# VCA822.net
KiCad netlist of a schematic drawn in Altium Designer
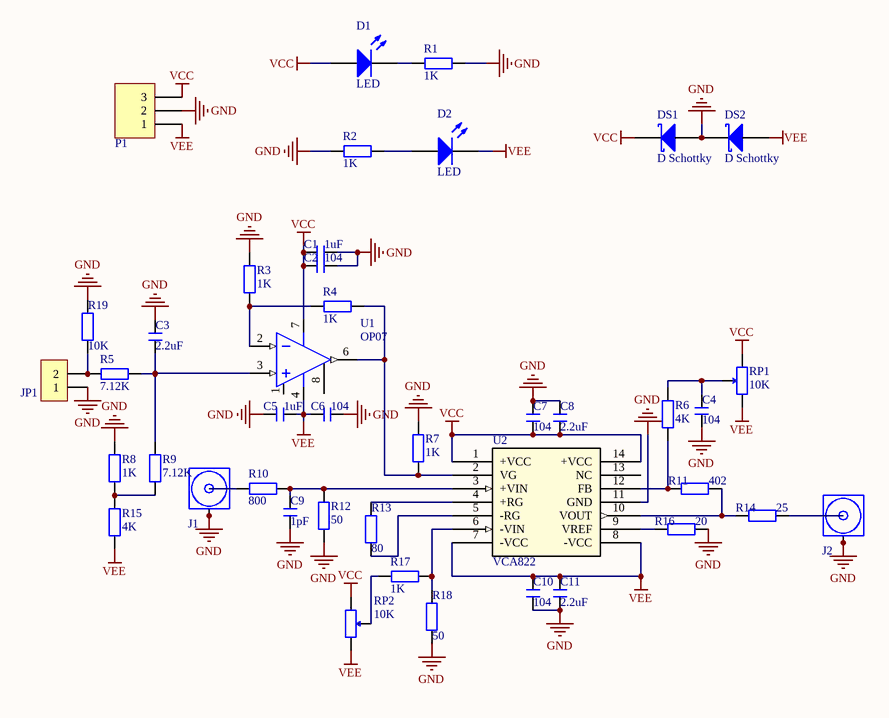
[diagram p0: VCA822.SchDoc]

(export (version "E")
  (design (tool "Eeschema 10.0.6"))
  (components
    (comp (ref "C1")
      (value "1uF")
      (footprint "C 0603")
      (description "无极性贴片电容")
      (fields (field (name "版权归属") "源创客"))
      (libsource (lib "电阻-电容-电感") (part "C"))
    )
    (comp (ref "C2")
      (value "104")
      (footprint "C 0603")
      (description "无极性贴片电容")
      (fields (field (name "版权归属") "源创客"))
      (libsource (lib "电阻-电容-电感") (part "C"))
    )
    (comp (ref "C3")
      (value "2.2uF")
      (footprint "C 0603")
      (description "无极性贴片电容")
      (fields (field (name "版权归属") "源创客"))
      (libsource (lib "电阻-电容-电感") (part "C"))
    )
    (comp (ref "C4")
      (value "104")
      (footprint "C 0603")
      (description "无极性贴片电容")
      (fields (field (name "版权归属") "源创客"))
      (libsource (lib "电阻-电容-电感") (part "C"))
    )
    (comp (ref "C5")
      (value "1uF")
      (footprint "C 0603")
      (description "无极性贴片电容")
      (fields (field (name "版权归属") "源创客"))
      (libsource (lib "电阻-电容-电感") (part "C"))
    )
    (comp (ref "C6")
      (value "104")
      (footprint "C 0603")
      (description "无极性贴片电容")
      (fields (field (name "版权归属") "源创客"))
      (libsource (lib "电阻-电容-电感") (part "C"))
    )
    (comp (ref "C7")
      (value "104")
      (footprint "C 0603")
      (description "无极性贴片电容")
      (fields (field (name "版权归属") "源创客"))
      (libsource (lib "电阻-电容-电感") (part "C"))
    )
    (comp (ref "C8")
      (value "2.2uF")
      (footprint "C 0603")
      (description "无极性贴片电容")
      (fields (field (name "版权归属") "源创客"))
      (libsource (lib "电阻-电容-电感") (part "C"))
    )
    (comp (ref "C9")
      (value "1pF")
      (footprint "C 0603")
      (description "无极性贴片电容")
      (fields (field (name "版权归属") "源创客"))
      (libsource (lib "电阻-电容-电感") (part "C"))
    )
    (comp (ref "C10")
      (value "104")
      (footprint "C 0603")
      (description "无极性贴片电容")
      (fields (field (name "版权归属") "源创客"))
      (libsource (lib "电阻-电容-电感") (part "C"))
    )
    (comp (ref "C11")
      (value "2.2uF")
      (footprint "C 0603")
      (description "无极性贴片电容")
      (fields (field (name "版权归属") "源创客"))
      (libsource (lib "电阻-电容-电感") (part "C"))
    )
    (comp (ref "D1")
      (value "LED")
      (footprint "LED_0805")
      (description "发光二极管")
      (fields (field (name "PUBLISHER") "Altium Limited"))
      (libsource (lib "LIB") (part "LED"))
    )
    (comp (ref "D2")
      (value "LED")
      (footprint "LED_0805")
      (description "发光二极管")
      (fields (field (name "PUBLISHER") "Altium Limited"))
      (libsource (lib "LIB") (part "LED"))
    )
    (comp (ref "DS1")
      (value "D Schottky")
      (footprint "DIODE-SMA")
      (description "Schottky Diode")
      (fields (field (name "PUBLISHER") "Altium Limited"))
      (libsource (lib "LIB") (part "D Schottky"))
    )
    (comp (ref "DS2")
      (value "D Schottky")
      (footprint "DIODE-SMA")
      (description "Schottky Diode")
      (fields (field (name "PUBLISHER") "Altium Limited"))
      (libsource (lib "LIB") (part "D Schottky"))
    )
    (comp (ref "J1") (value "COAX") (footprint "MCX5.08-5-H") (libsource (lib "LIB") (part "COAX")))
    (comp (ref "J2") (value "COAX") (footprint "MCX5.08-5-H") (libsource (lib "LIB") (part "COAX")))
    (comp (ref "JP1")
      (value "HDR-1X2")
      (footprint "HDR-1X2")
      (description "2P接插件")
      (fields (field (name "版权归属") "源创客"))
      (libsource (lib "接插件") (part "Header 2"))
    )
    (comp (ref "P1")
      (value "Header 3")
      (footprint "HDR3X1_B2")
      (description "接插件")
      (fields (field (name "PUBLISHER") "Altium Limited"))
      (libsource (lib "LIB") (part "Header 3"))
    )
    (comp (ref "R1")
      (value "1K")
      (footprint "R 0805")
      (description "贴片电阻")
      (fields (field (name "版权归属") "源创客"))
      (libsource (lib "电阻-电容-电感") (part "R"))
    )
    (comp (ref "R2")
      (value "1K")
      (footprint "R 0805")
      (description "贴片电阻")
      (fields (field (name "版权归属") "源创客"))
      (libsource (lib "电阻-电容-电感") (part "R"))
    )
    (comp (ref "R3")
      (value "1K")
      (footprint "R 0603")
      (description "贴片电阻")
      (fields (field (name "版权归属") "源创客"))
      (libsource (lib "电阻-电容-电感") (part "R"))
    )
    (comp (ref "R4")
      (value "1K")
      (footprint "R 0603")
      (description "贴片电阻")
      (fields (field (name "版权归属") "源创客"))
      (libsource (lib "电阻-电容-电感") (part "R"))
    )
    (comp (ref "R5")
      (value "7.12K")
      (footprint "R 0603")
      (description "贴片电阻")
      (fields (field (name "版权归属") "源创客"))
      (libsource (lib "电阻-电容-电感") (part "R"))
    )
    (comp (ref "R6")
      (value "4K")
      (footprint "R 0603")
      (description "贴片电阻")
      (fields (field (name "版权归属") "源创客"))
      (libsource (lib "电阻-电容-电感") (part "R"))
    )
    (comp (ref "R7")
      (value "1K")
      (footprint "R 0603")
      (description "贴片电阻")
      (fields (field (name "版权归属") "源创客"))
      (libsource (lib "电阻-电容-电感") (part "R"))
    )
    (comp (ref "R8")
      (value "1K")
      (footprint "R 0603")
      (description "贴片电阻")
      (fields (field (name "版权归属") "源创客"))
      (libsource (lib "电阻-电容-电感") (part "R"))
    )
    (comp (ref "R9")
      (value "7.12K")
      (footprint "R 0603")
      (description "贴片电阻")
      (fields (field (name "版权归属") "源创客"))
      (libsource (lib "电阻-电容-电感") (part "R"))
    )
    (comp (ref "R10")
      (value "800")
      (footprint "R 0603")
      (description "贴片电阻")
      (fields (field (name "版权归属") "源创客"))
      (libsource (lib "电阻-电容-电感") (part "R"))
    )
    (comp (ref "R11")
      (value "402")
      (footprint "R 0603")
      (description "贴片电阻")
      (fields (field (name "版权归属") "源创客"))
      (libsource (lib "电阻-电容-电感") (part "R"))
    )
    (comp (ref "R12")
      (value "50")
      (footprint "R 0603")
      (description "贴片电阻")
      (fields (field (name "版权归属") "源创客"))
      (libsource (lib "电阻-电容-电感") (part "R"))
    )
    (comp (ref "R13")
      (value "80")
      (footprint "R 0603")
      (description "贴片电阻")
      (fields (field (name "版权归属") "源创客"))
      (libsource (lib "电阻-电容-电感") (part "R"))
    )
    (comp (ref "R14")
      (value "25")
      (footprint "R 0603")
      (description "贴片电阻")
      (fields (field (name "版权归属") "源创客"))
      (libsource (lib "电阻-电容-电感") (part "R"))
    )
    (comp (ref "R15")
      (value "4K")
      (footprint "R 0603")
      (description "贴片电阻")
      (fields (field (name "版权归属") "源创客"))
      (libsource (lib "电阻-电容-电感") (part "R"))
    )
    (comp (ref "R16")
      (value "20")
      (footprint "R 0603")
      (description "贴片电阻")
      (fields (field (name "版权归属") "源创客"))
      (libsource (lib "电阻-电容-电感") (part "R"))
    )
    (comp (ref "R17")
      (value "1K")
      (footprint "R 0603")
      (description "贴片电阻")
      (fields (field (name "版权归属") "源创客"))
      (libsource (lib "电阻-电容-电感") (part "R"))
    )
    (comp (ref "R18")
      (value "50")
      (footprint "R 0603")
      (description "贴片电阻")
      (fields (field (name "版权归属") "源创客"))
      (libsource (lib "电阻-电容-电感") (part "R"))
    )
    (comp (ref "R19")
      (value "10K")
      (footprint "R 0603")
      (description "贴片电阻")
      (fields (field (name "版权归属") "源创客"))
      (libsource (lib "电阻-电容-电感") (part "R"))
    )
    (comp (ref "RP1")
      (value "10K")
      (footprint "3296W")
      (description "插件单联电位器")
      (fields (field (name "版权归属") "源创客"))
      (libsource (lib "电阻-电容-电感") (part "RP-ID"))
    )
    (comp (ref "RP2")
      (value "10K")
      (footprint "3296W")
      (description "插件单联电位器")
      (fields (field (name "版权归属") "源创客"))
      (libsource (lib "电阻-电容-电感") (part "RP-ID"))
    )
    (comp (ref "U1")
      (value "OP07")
      (footprint "SO8_L")
      (description "Precision Operational Amplifiers")
      (libsource (lib "LIB") (part "OP07"))
    )
    (comp (ref "U2")
      (value "VCA822")
      (footprint "SOIC14_N")
      (description "VCA822 Wideband, > 40-dB Gain Adjust Range, Linear in V/V Variable Gain Amplifier")
      (fields (field (name "MANUFACTURER") "Texas Instruments") (field (name "GENERIC_PART_NUMBER") "VCA821"))
      (libsource (lib "LIB") (part "VCA822"))
    )
  )
  (nets
    (net (code "1") (name "GND") (class "Default")
      (node (ref "C1") (pin "1") (pinfunction "1_1") (pintype "passive"))
      (node (ref "C10") (pin "2") (pinfunction "2_2") (pintype "passive"))
      (node (ref "C11") (pin "1") (pinfunction "1_1") (pintype "passive"))
      (node (ref "C2") (pin "1") (pinfunction "1_1") (pintype "passive"))
      (node (ref "C3") (pin "1") (pinfunction "1_1") (pintype "passive"))
      (node (ref "C4") (pin "1") (pinfunction "1_1") (pintype "passive"))
      (node (ref "C5") (pin "2") (pinfunction "2_2") (pintype "passive"))
      (node (ref "C6") (pin "1") (pinfunction "1_1") (pintype "passive"))
      (node (ref "C7") (pin "2") (pinfunction "2_2") (pintype "passive"))
      (node (ref "C8") (pin "2") (pinfunction "2_2") (pintype "passive"))
      (node (ref "C9") (pin "2") (pinfunction "2_2") (pintype "passive"))
      (node (ref "DS1") (pin "1") (pinfunction "1_1") (pintype "passive"))
      (node (ref "DS2") (pin "2") (pinfunction "2_2") (pintype "passive"))
      (node (ref "J1") (pin "2") (pinfunction "GND_2") (pintype "passive"))
      (node (ref "J1") (pin "3") (pinfunction "GND_3") (pintype "passive"))
      (node (ref "J1") (pin "4") (pinfunction "GND_4") (pintype "passive"))
      (node (ref "J1") (pin "5") (pinfunction "GND_5") (pintype "passive"))
      (node (ref "J2") (pin "2") (pinfunction "GND_2") (pintype "passive"))
      (node (ref "J2") (pin "3") (pinfunction "GND_3") (pintype "passive"))
      (node (ref "J2") (pin "4") (pinfunction "GND_4") (pintype "passive"))
      (node (ref "J2") (pin "5") (pinfunction "GND_5") (pintype "passive"))
      (node (ref "JP1") (pin "1") (pinfunction "1_1") (pintype "passive"))
      (node (ref "P1") (pin "2") (pinfunction "2_2") (pintype "passive"))
      (node (ref "R1") (pin "2") (pinfunction "2_2") (pintype "passive"))
      (node (ref "R12") (pin "1") (pinfunction "1_1") (pintype "passive"))
      (node (ref "R16") (pin "2") (pinfunction "2_2") (pintype "passive"))
      (node (ref "R18") (pin "1") (pinfunction "1_1") (pintype "passive"))
      (node (ref "R19") (pin "2") (pinfunction "2_2") (pintype "passive"))
      (node (ref "R2") (pin "1") (pinfunction "1_1") (pintype "passive"))
      (node (ref "R3") (pin "2") (pinfunction "2_2") (pintype "passive"))
      (node (ref "R7") (pin "1") (pinfunction "1_1") (pintype "passive"))
      (node (ref "R8") (pin "2") (pinfunction "2_2") (pintype "passive"))
      (node (ref "U2") (pin "11") (pinfunction "GND_11") (pintype "power_in"))
    )
    (net (code "2") (name "Net-(C4-Pad2)") (class "Default")
      (node (ref "C4") (pin "2") (pinfunction "2_2") (pintype "passive"))
      (node (ref "R6") (pin "2") (pinfunction "2_2") (pintype "passive"))
      (node (ref "RP1") (pin "2") (pinfunction "2_2") (pintype "passive"))
    )
    (net (code "3") (name "Net-(D1-K)") (class "Default")
      (node (ref "D1") (pin "2") (pinfunction "K_2") (pintype "passive"))
      (node (ref "R1") (pin "1") (pinfunction "1_1") (pintype "passive"))
    )
    (net (code "4") (name "Net-(D2-A)") (class "Default")
      (node (ref "D2") (pin "1") (pinfunction "A_1") (pintype "passive"))
      (node (ref "R2") (pin "2") (pinfunction "2_2") (pintype "passive"))
    )
    (net (code "5") (name "Net-(J1-Signal)") (class "Default")
      (node (ref "J1") (pin "1") (pinfunction "Signal_1") (pintype "passive"))
      (node (ref "R10") (pin "2") (pinfunction "2_2") (pintype "passive"))
    )
    (net (code "6") (name "Net-(J2-Signal)") (class "Default")
      (node (ref "J2") (pin "1") (pinfunction "Signal_1") (pintype "passive"))
      (node (ref "R14") (pin "2") (pinfunction "2_2") (pintype "passive"))
    )
    (net (code "7") (name "Net-(JP1-Pad2)") (class "Default")
      (node (ref "JP1") (pin "2") (pinfunction "2_2") (pintype "passive"))
      (node (ref "R19") (pin "1") (pinfunction "1_1") (pintype "passive"))
      (node (ref "R5") (pin "2") (pinfunction "2_2") (pintype "passive"))
    )
    (net (code "8") (name "Net-(R15-Pad2)") (class "Default")
      (node (ref "R15") (pin "2") (pinfunction "2_2") (pintype "passive"))
      (node (ref "R8") (pin "1") (pinfunction "1_1") (pintype "passive"))
      (node (ref "R9") (pin "2") (pinfunction "2_2") (pintype "passive"))
    )
    (net (code "9") (name "Net-(R17-Pad2)") (class "Default")
      (node (ref "R17") (pin "2") (pinfunction "2_2") (pintype "passive"))
      (node (ref "RP2") (pin "2") (pinfunction "2_2") (pintype "passive"))
    )
    (net (code "10") (name "Net-(U1-IN+)") (class "Default")
      (node (ref "C3") (pin "2") (pinfunction "2_2") (pintype "passive"))
      (node (ref "R5") (pin "1") (pinfunction "1_1") (pintype "passive"))
      (node (ref "R9") (pin "1") (pinfunction "1_1") (pintype "passive"))
      (node (ref "U1") (pin "3") (pinfunction "IN+_3") (pintype "input"))
    )
    (net (code "11") (name "Net-(U1-IN-)") (class "Default")
      (node (ref "R3") (pin "1") (pinfunction "1_1") (pintype "passive"))
      (node (ref "R4") (pin "1") (pinfunction "1_1") (pintype "passive"))
      (node (ref "U1") (pin "2") (pinfunction "IN-_2") (pintype "input"))
    )
    (net (code "12") (name "Net-(U1-OUT)") (class "Default")
      (node (ref "R4") (pin "2") (pinfunction "2_2") (pintype "passive"))
      (node (ref "R7") (pin "2") (pinfunction "2_2") (pintype "passive"))
      (node (ref "U1") (pin "6") (pinfunction "OUT_6") (pintype "output"))
      (node (ref "U2") (pin "2") (pinfunction "VG_2") (pintype "passive"))
    )
    (net (code "13") (name "Net-(U2-+RG)") (class "Default")
      (node (ref "R13") (pin "2") (pinfunction "2_2") (pintype "passive"))
      (node (ref "U2") (pin "4") (pinfunction "+RG_4") (pintype "passive"))
    )
    (net (code "14") (name "Net-(U2-+VIN)") (class "Default")
      (node (ref "C9") (pin "1") (pinfunction "1_1") (pintype "passive"))
      (node (ref "R10") (pin "1") (pinfunction "1_1") (pintype "passive"))
      (node (ref "R12") (pin "2") (pinfunction "2_2") (pintype "passive"))
      (node (ref "U2") (pin "3") (pinfunction "+VIN_3") (pintype "input"))
    )
    (net (code "15") (name "Net-(U2--RG)") (class "Default")
      (node (ref "R13") (pin "1") (pinfunction "1_1") (pintype "passive"))
      (node (ref "U2") (pin "5") (pinfunction "-RG_5") (pintype "passive"))
    )
    (net (code "16") (name "Net-(U2--VIN)") (class "Default")
      (node (ref "R17") (pin "1") (pinfunction "1_1") (pintype "passive"))
      (node (ref "R18") (pin "2") (pinfunction "2_2") (pintype "passive"))
      (node (ref "U2") (pin "6") (pinfunction "-VIN_6") (pintype "input"))
    )
    (net (code "17") (name "Net-(U2-FB)") (class "Default")
      (node (ref "R11") (pin "1") (pinfunction "1_1") (pintype "passive"))
      (node (ref "R6") (pin "1") (pinfunction "1_1") (pintype "passive"))
      (node (ref "U2") (pin "12") (pinfunction "FB_12") (pintype "passive"))
    )
    (net (code "18") (name "Net-(U2-VOUT)") (class "Default")
      (node (ref "R11") (pin "2") (pinfunction "2_2") (pintype "passive"))
      (node (ref "R14") (pin "1") (pinfunction "1_1") (pintype "passive"))
      (node (ref "U2") (pin "10") (pinfunction "VOUT_10") (pintype "output"))
    )
    (net (code "19") (name "Net-(U2-VREF)") (class "Default")
      (node (ref "R16") (pin "1") (pinfunction "1_1") (pintype "passive"))
      (node (ref "U2") (pin "9") (pinfunction "VREF_9") (pintype "passive"))
    )
    (net (code "20") (name "VCC") (class "Default")
      (node (ref "C1") (pin "2") (pinfunction "2_2") (pintype "passive"))
      (node (ref "C2") (pin "2") (pinfunction "2_2") (pintype "passive"))
      (node (ref "C7") (pin "1") (pinfunction "1_1") (pintype "passive"))
      (node (ref "C8") (pin "1") (pinfunction "1_1") (pintype "passive"))
      (node (ref "D1") (pin "1") (pinfunction "A_1") (pintype "passive"))
      (node (ref "DS1") (pin "2") (pinfunction "2_2") (pintype "passive"))
      (node (ref "P1") (pin "3") (pinfunction "3_3") (pintype "passive"))
      (node (ref "RP1") (pin "1") (pinfunction "1_1") (pintype "passive"))
      (node (ref "RP2") (pin "1") (pinfunction "1_1") (pintype "passive"))
      (node (ref "U1") (pin "7") (pinfunction "V+_7") (pintype "power_in"))
      (node (ref "U2") (pin "1") (pinfunction "+VCC_1") (pintype "power_in"))
      (node (ref "U2") (pin "14") (pinfunction "+VCC_14") (pintype "power_in"))
    )
    (net (code "21") (name "VEE") (class "Default")
      (node (ref "C10") (pin "1") (pinfunction "1_1") (pintype "passive"))
      (node (ref "C11") (pin "2") (pinfunction "2_2") (pintype "passive"))
      (node (ref "C5") (pin "1") (pinfunction "1_1") (pintype "passive"))
      (node (ref "C6") (pin "2") (pinfunction "2_2") (pintype "passive"))
      (node (ref "D2") (pin "2") (pinfunction "K_2") (pintype "passive"))
      (node (ref "DS2") (pin "1") (pinfunction "1_1") (pintype "passive"))
      (node (ref "P1") (pin "1") (pinfunction "1_1") (pintype "passive"))
      (node (ref "R15") (pin "1") (pinfunction "1_1") (pintype "passive"))
      (node (ref "RP1") (pin "3") (pinfunction "3_3") (pintype "passive"))
      (node (ref "RP2") (pin "3") (pinfunction "3_3") (pintype "passive"))
      (node (ref "U1") (pin "4") (pinfunction "V-_4") (pintype "power_in"))
      (node (ref "U2") (pin "7") (pinfunction "-VCC_7") (pintype "power_in"))
      (node (ref "U2") (pin "8") (pinfunction "-VCC_8") (pintype "power_in"))
    )
    (net (code "22") (name "unconnected-(U1-OFFSET_N1-Pad1)") (class "Default")
      (node (ref "U1") (pin "1") (pinfunction "OFFSET_N1_1") (pintype "passive"))
    )
    (net (code "23") (name "unconnected-(U1-OFFSET_N2-Pad8)") (class "Default")
      (node (ref "U1") (pin "8") (pinfunction "OFFSET_N2_8") (pintype "passive"))
    )
    (net (code "24") (name "unconnected-(U2-NC-Pad13)") (class "Default")
      (node (ref "U2") (pin "13") (pinfunction "NC_13") (pintype "passive"))
    )
  )
)
